# Laser_Shield_Eth.net
KiCad netlist of a schematic drawn in EAGLE
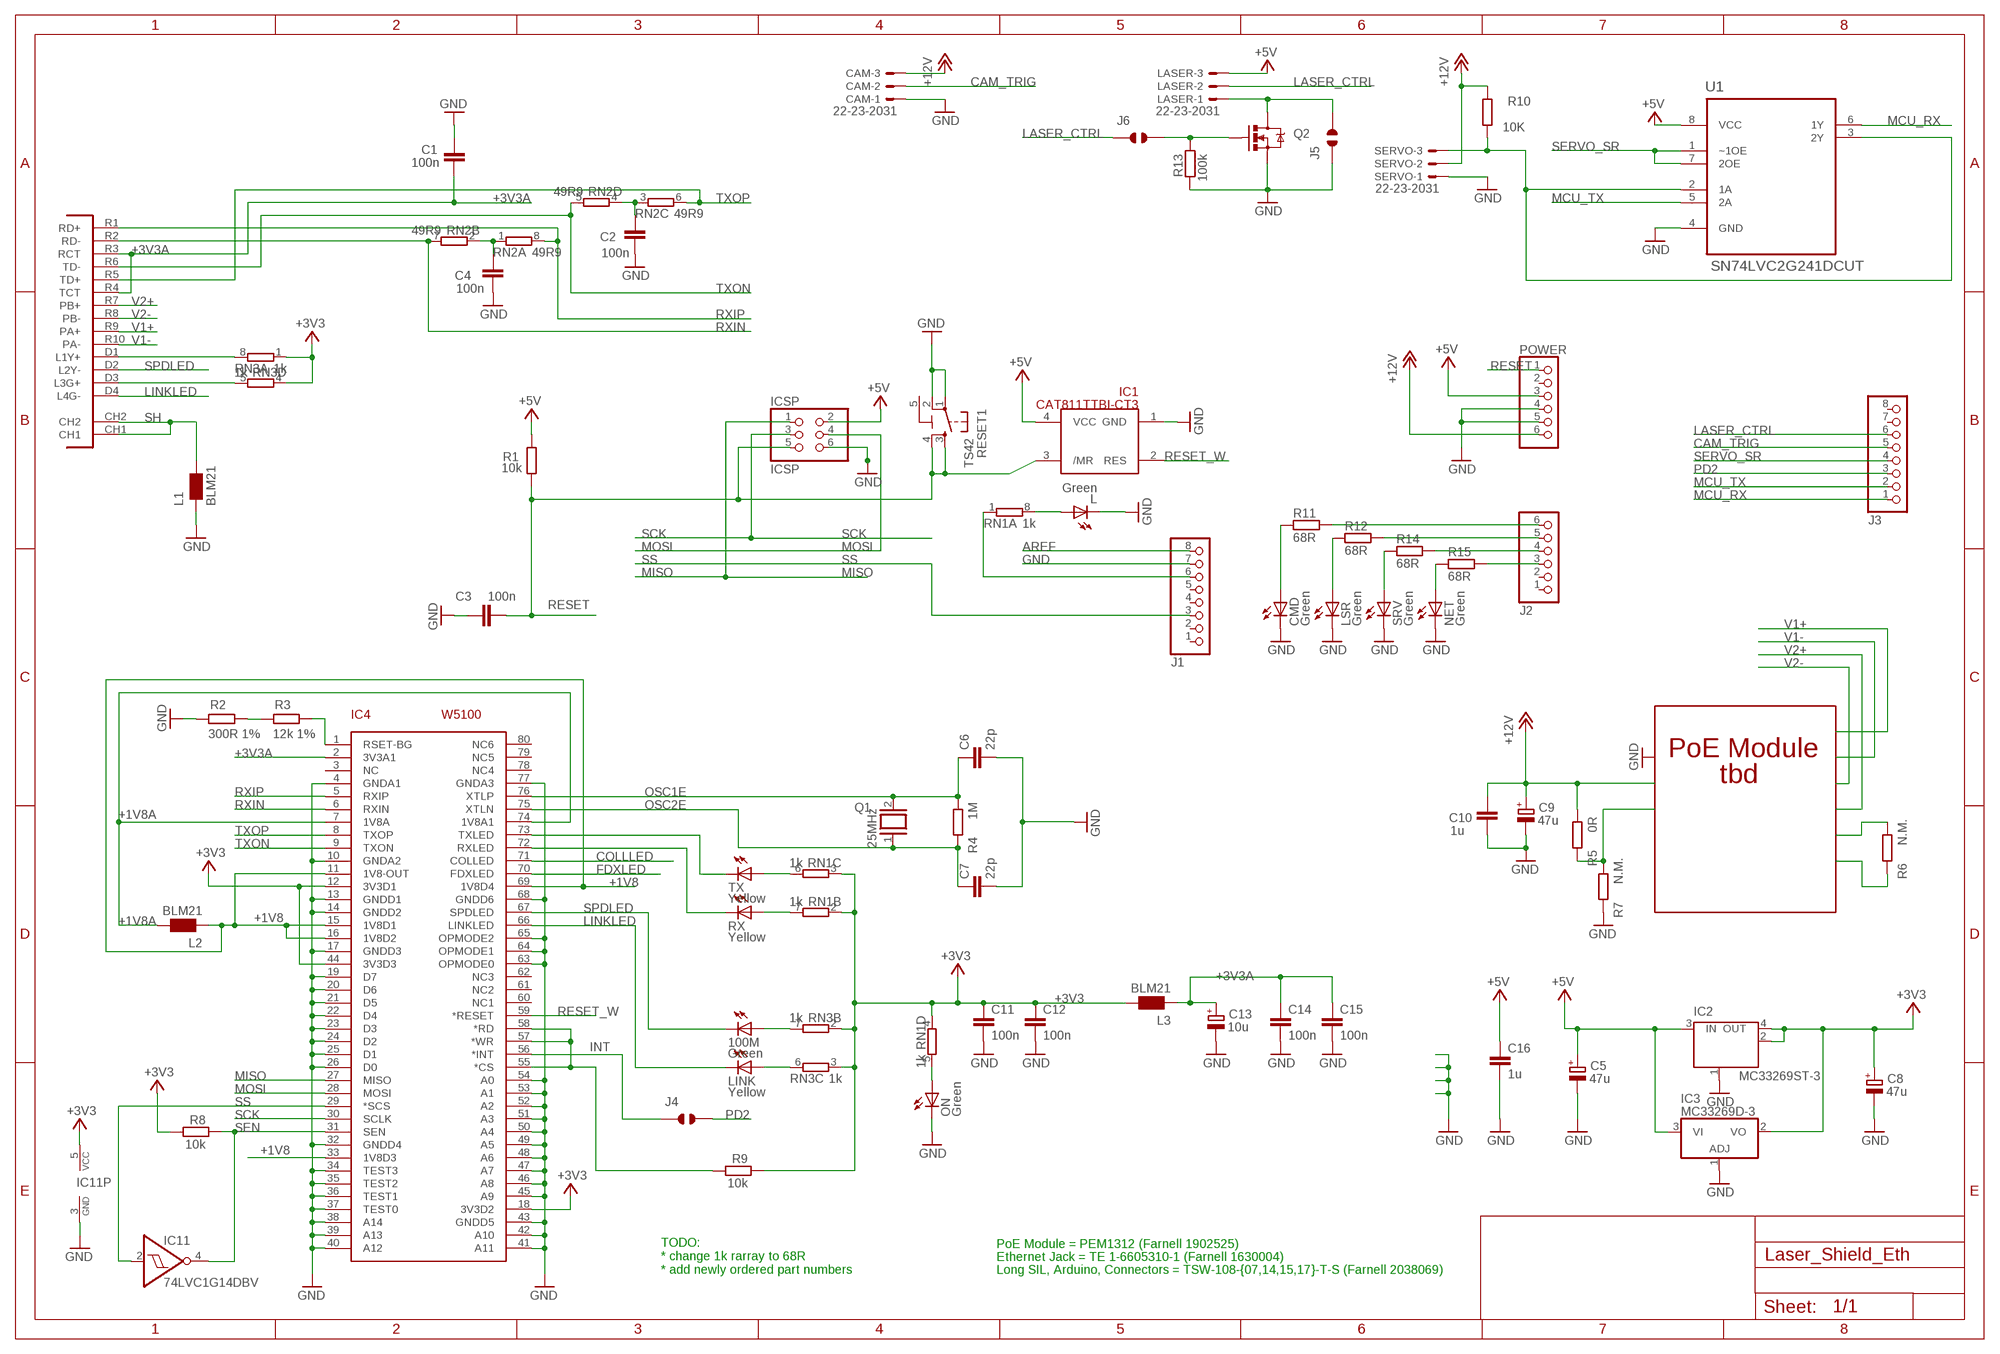
[diagram p0: schematic, sheet 1]

(export (version "E")
  (design (tool "Eeschema 10.0.6"))
  (components
    (comp (ref "100M")
      (value "Green")
      (footprint "eagle-import:CHIPLED_0805")
      (libsource (lib "eagle-import") (part "LEDCHIPLED_0805"))
    )
    (comp (ref "C1")
      (value "100n")
      (footprint "eagle-import:C0603-ROUND")
      (libsource (lib "eagle-import") (part "C-EUC0603"))
    )
    (comp (ref "C2")
      (value "100n")
      (footprint "eagle-import:C0603-ROUND")
      (libsource (lib "eagle-import") (part "C-EUC0603"))
    )
    (comp (ref "C3")
      (value "100n")
      (footprint "eagle-import:C0603-ROUND")
      (libsource (lib "eagle-import") (part "C-EUC0603"))
    )
    (comp (ref "C4")
      (value "100n")
      (footprint "eagle-import:C0603-ROUND")
      (libsource (lib "eagle-import") (part "C-EUC0603"))
    )
    (comp (ref "C5")
      (value "47u")
      (footprint "eagle-import:PANASONIC_D")
      (libsource (lib "eagle-import") (part "CPOL-EUD"))
    )
    (comp (ref "C6")
      (value "22p")
      (footprint "eagle-import:C0603-ROUND")
      (libsource (lib "eagle-import") (part "C-EUC0603"))
    )
    (comp (ref "C7")
      (value "22p")
      (footprint "eagle-import:C0603-ROUND")
      (libsource (lib "eagle-import") (part "C-EUC0603"))
    )
    (comp (ref "C8")
      (value "47u")
      (footprint "eagle-import:PANASONIC_D")
      (libsource (lib "eagle-import") (part "CPOL-EUD"))
    )
    (comp (ref "C9")
      (value "47u")
      (footprint "eagle-import:PANASONIC_D")
      (libsource (lib "eagle-import") (part "CPOL-EUD"))
    )
    (comp (ref "C10")
      (value "1u")
      (footprint "eagle-import:C0603-ROUND")
      (libsource (lib "eagle-import") (part "C-EUC0603"))
    )
    (comp (ref "C11")
      (value "100n")
      (footprint "eagle-import:C0603-ROUND")
      (libsource (lib "eagle-import") (part "C-EUC0603"))
    )
    (comp (ref "C12")
      (value "100n")
      (footprint "eagle-import:C0603-ROUND")
      (libsource (lib "eagle-import") (part "C-EUC0603"))
    )
    (comp (ref "C13")
      (value "10u")
      (footprint "eagle-import:SMC_B")
      (libsource (lib "eagle-import") (part "CPOL-EUSMCB"))
    )
    (comp (ref "C14")
      (value "100n")
      (footprint "eagle-import:C0603-ROUND")
      (libsource (lib "eagle-import") (part "C-EUC0603"))
    )
    (comp (ref "C15")
      (value "100n")
      (footprint "eagle-import:C0603-ROUND")
      (libsource (lib "eagle-import") (part "C-EUC0603"))
    )
    (comp (ref "C16")
      (value "1u")
      (footprint "eagle-import:C0603-ROUND")
      (libsource (lib "eagle-import") (part "C-EUC0603"))
    )
    (comp (ref "CAM")
      (value "22-23-2031")
      (footprint "eagle-import:22-23-2031")
      (fields (field (name "MF") "MOLEX"))
      (libsource (lib "eagle-import") (part "22-23-2031"))
    )
    (comp (ref "CMD")
      (value "Green")
      (footprint "eagle-import:CHIPLED_0805")
      (libsource (lib "eagle-import") (part "LEDCHIPLED_0805"))
    )
    (comp (ref "IC1")
      (value "CAT811TTBI-CT3")
      (footprint "eagle-import:SOT143")
      (fields (field (name "MPN") "STM812LW16F"))
      (libsource (lib "eagle-import") (part "STM812"))
    )
    (comp (ref "IC2")
      (value "MC33269ST-3")
      (footprint "eagle-import:SOT223")
      (libsource (lib "eagle-import") (part "MC33269ST-3.3T3"))
    )
    (comp (ref "IC3")
      (value "MC33269D-3")
      (footprint "eagle-import:DPACK")
      (libsource (lib "eagle-import") (part "MC33269?D-3.3"))
    )
    (comp (ref "IC4")
      (value "W5100")
      (footprint "eagle-import:SQFP-S-10X10-80")
      (libsource (lib "eagle-import") (part "W5100"))
    )
    (comp (ref "IC11")
      (value "74LVC1G14DBV")
      (footprint "eagle-import:SOT23-5")
      (fields (field (name "MPN") "SN74LVC1G14DBVT") (field (name "OC_FARNELL") "1236328"))
      (libsource (lib "eagle-import") (part "741G14DBVLVC"))
    )
    (comp (ref "ICSP")
      (value "ICSP")
      (footprint "eagle-import:2X03")
      (libsource (lib "eagle-import") (part "PINHD-2X3"))
    )
    (comp (ref "J1")
      (value "PINHD-1X8")
      (footprint "eagle-import:1X08")
      (libsource (lib "eagle-import") (part "PINHD-1X8"))
    )
    (comp (ref "J2")
      (value "PINHD-1X6")
      (footprint "eagle-import:1X06")
      (libsource (lib "eagle-import") (part "PINHD-1X6"))
    )
    (comp (ref "J3")
      (value "PINHD-1X8")
      (footprint "eagle-import:1X08")
      (libsource (lib "eagle-import") (part "PINHD-1X8"))
    )
    (comp (ref "J4")
      (value "JUMPER_SOLDER_1X2")
      (footprint "eagle-import:JUMPER_SOLDER_1X2")
      (libsource (lib "eagle-import") (part "JUMPER_SOLDER_1X2"))
    )
    (comp (ref "J5")
      (value "JUMPER_SOLDER_1X2")
      (footprint "eagle-import:JUMPER_SOLDER_1X2")
      (libsource (lib "eagle-import") (part "JUMPER_SOLDER_1X2"))
    )
    (comp (ref "J6")
      (value "JUMPER_SOLDER_1X2")
      (footprint "eagle-import:JUMPER_SOLDER_1X2")
      (libsource (lib "eagle-import") (part "JUMPER_SOLDER_1X2"))
    )
    (comp (ref "L")
      (value "Green")
      (footprint "eagle-import:CHIPLED_0805")
      (libsource (lib "eagle-import") (part "LEDCHIPLED_0805"))
    )
    (comp (ref "L1")
      (value "BLM21")
      (footprint "eagle-import:0805")
      (libsource (lib "eagle-import") (part "WE-CBF_0805"))
    )
    (comp (ref "L2")
      (value "BLM21")
      (footprint "eagle-import:0805")
      (libsource (lib "eagle-import") (part "WE-CBF_0805"))
    )
    (comp (ref "L3")
      (value "BLM21")
      (footprint "eagle-import:0805")
      (libsource (lib "eagle-import") (part "WE-CBF_0805"))
    )
    (comp (ref "LASER")
      (value "22-23-2031")
      (footprint "eagle-import:22-23-2031")
      (fields (field (name "MF") "MOLEX"))
      (libsource (lib "eagle-import") (part "22-23-2031"))
    )
    (comp (ref "LINK")
      (value "Yellow")
      (footprint "eagle-import:CHIPLED_0805")
      (libsource (lib "eagle-import") (part "LEDCHIPLED_0805"))
    )
    (comp (ref "LSR")
      (value "Green")
      (footprint "eagle-import:CHIPLED_0805")
      (libsource (lib "eagle-import") (part "LEDCHIPLED_0805"))
    )
    (comp (ref "NET")
      (value "Green")
      (footprint "eagle-import:CHIPLED_0805")
      (libsource (lib "eagle-import") (part "LEDCHIPLED_0805"))
    )
    (comp (ref "ON")
      (value "Green")
      (footprint "eagle-import:CHIPLED_0805")
      (libsource (lib "eagle-import") (part "LEDCHIPLED_0805"))
    )
    (comp (ref "POWER")
      (value "PINHD-1X6")
      (footprint "eagle-import:1X06")
      (libsource (lib "eagle-import") (part "PINHD-1X6"))
    )
    (comp (ref "Q1")
      (value "25MHz")
      (footprint "eagle-import:QS")
      (libsource (lib "eagle-import") (part "XTAL/S"))
    )
    (comp (ref "Q2")
      (value "MOSFET-NCHANNELSMD")
      (footprint "eagle-import:SOT23-3")
      (libsource (lib "eagle-import") (part "MOSFET-NCHANNELSMD"))
    )
    (comp (ref "R1")
      (value "10k")
      (footprint "eagle-import:R0603-ROUND")
      (libsource (lib "eagle-import") (part "R-EU_0603-RND"))
    )
    (comp (ref "R2")
      (value "300R 1%")
      (footprint "eagle-import:R0603-ROUND")
      (libsource (lib "eagle-import") (part "R-EU_0603-RND"))
    )
    (comp (ref "R3")
      (value "12k 1%")
      (footprint "eagle-import:R0603-ROUND")
      (libsource (lib "eagle-import") (part "R-EU_0603-RND"))
    )
    (comp (ref "R4")
      (value "1M")
      (footprint "eagle-import:R0603-ROUND")
      (libsource (lib "eagle-import") (part "R-EU_0603-RND"))
    )
    (comp (ref "R5")
      (value "0R")
      (footprint "eagle-import:R0603-ROUND")
      (libsource (lib "eagle-import") (part "R-EU_0603-RND"))
    )
    (comp (ref "R6")
      (value "N.M.")
      (footprint "eagle-import:R0603-ROUND")
      (libsource (lib "eagle-import") (part "R-EU_0603-RND"))
    )
    (comp (ref "R7")
      (value "N.M.")
      (footprint "eagle-import:R0603-ROUND")
      (libsource (lib "eagle-import") (part "R-EU_0603-RND"))
    )
    (comp (ref "R8")
      (value "10k")
      (footprint "eagle-import:R0603-ROUND")
      (libsource (lib "eagle-import") (part "R-EU_0603-RND"))
    )
    (comp (ref "R9")
      (value "10k")
      (footprint "eagle-import:R0603-ROUND")
      (libsource (lib "eagle-import") (part "R-EU_R0603"))
    )
    (comp (ref "R10")
      (value "10K")
      (footprint "eagle-import:R0603-ROUND")
      (libsource (lib "eagle-import") (part "R-EU_0603-RND"))
    )
    (comp (ref "R11")
      (value "68R")
      (footprint "eagle-import:R0603-ROUND")
      (libsource (lib "eagle-import") (part "R-EU_R0603"))
    )
    (comp (ref "R12")
      (value "68R")
      (footprint "eagle-import:R0603-ROUND")
      (libsource (lib "eagle-import") (part "R-EU_R0603"))
    )
    (comp (ref "R13")
      (value "100k")
      (footprint "eagle-import:R0603-ROUND")
      (libsource (lib "eagle-import") (part "R-EU_R0603"))
    )
    (comp (ref "R14")
      (value "68R")
      (footprint "eagle-import:R0603-ROUND")
      (libsource (lib "eagle-import") (part "R-EU_R0603"))
    )
    (comp (ref "R15")
      (value "68R")
      (footprint "eagle-import:R0603-ROUND")
      (libsource (lib "eagle-import") (part "R-EU_R0603"))
    )
    (comp (ref "RESET1")
      (value "TS42")
      (footprint "eagle-import:TS42")
      (libsource (lib "eagle-import") (part "TS42"))
    )
    (comp (ref "RN1")
      (value "1k")
      (footprint "eagle-import:CAY16")
      (fields (field (name "MPN") "CAY16-102J4LF") (field (name "OC_FARNELL") "1770133"))
      (libsource (lib "eagle-import") (part "4R-NCAY16"))
    )
    (comp (ref "RN2")
      (value "49R9")
      (footprint "eagle-import:CAY16")
      (fields (field (name "MPN") "CAY16-49R9F4LF") (field (name "OC_FARNELL") "2113092"))
      (libsource (lib "eagle-import") (part "4R-NCAY16"))
    )
    (comp (ref "RN3")
      (value "1k")
      (footprint "eagle-import:CAY16")
      (fields (field (name "MPN") "CAY16-102J4LF") (field (name "OC_FARNELL") "1770133"))
      (libsource (lib "eagle-import") (part "4R-NCAY16"))
    )
    (comp (ref "RX")
      (value "Yellow")
      (footprint "eagle-import:CHIPLED_0805")
      (libsource (lib "eagle-import") (part "LEDCHIPLED_0805"))
    )
    (comp (ref "SERVO")
      (value "22-23-2031")
      (footprint "eagle-import:22-23-2031")
      (fields
        (field (name "MF") "MOLEX")
        (field (name "MPN") "22-03-5035")
        (field (name "OC_FARNELL") "9979620")
      )
      (libsource (lib "eagle-import") (part "22-23-2031"))
    )
    (comp (ref "SRV")
      (value "Green")
      (footprint "eagle-import:CHIPLED_0805")
      (libsource (lib "eagle-import") (part "LEDCHIPLED_0805"))
    )
    (comp (ref "TX")
      (value "Yellow")
      (footprint "eagle-import:CHIPLED_0805")
      (libsource (lib "eagle-import") (part "LEDCHIPLED_0805"))
    )
    (comp (ref "U$1")
      (value "POE-RJ45")
      (footprint "eagle-import:POE-RJ45")
      (libsource (lib "eagle-import") (part "POE-RJ45"))
    )
    (comp (ref "U1")
      (value "SN74LVC2G241DCUT")
      (footprint "eagle-import:SOP50P310X90-8N")
      (libsource (lib "eagle-import") (part "SN74LVC2G241DCUT"))
    )
  )
  (nets
    (net (code "1") (name "+3V3") (class "Default")
      (node (ref "C11") (pin "1") (pinfunction "1_1") (pintype "passive"))
      (node (ref "C12") (pin "1") (pinfunction "1_1") (pintype "passive"))
      (node (ref "C8") (pin "+") (pinfunction "+_+") (pintype "passive"))
      (node (ref "IC11") (pin "5") (pinfunction "VCC_5") (pintype "power_in"))
      (node (ref "IC2") (pin "2") (pinfunction "OUT_2") (pintype "passive"))
      (node (ref "IC2") (pin "4") (pinfunction "OUT_4") (pintype "passive"))
      (node (ref "IC3") (pin "2") (pinfunction "VO_2") (pintype "passive"))
      (node (ref "IC4") (pin "12") (pinfunction "3V3D1_12") (pintype "power_in"))
      (node (ref "IC4") (pin "18") (pinfunction "3V3D2_18") (pintype "power_in"))
      (node (ref "IC4") (pin "44") (pinfunction "3V3D3_44") (pintype "power_in"))
      (node (ref "L3") (pin "2") (pinfunction "2_2") (pintype "passive"))
      (node (ref "R8") (pin "1") (pinfunction "1_1") (pintype "passive"))
      (node (ref "R9") (pin "2") (pinfunction "2_2") (pintype "passive"))
      (node (ref "RN1") (pin "2") (pinfunction "1_2") (pintype "passive"))
      (node (ref "RN1") (pin "3") (pinfunction "1_3") (pintype "passive"))
      (node (ref "RN1") (pin "4") (pinfunction "1_4") (pintype "passive"))
      (node (ref "RN3") (pin "1") (pinfunction "1_1") (pintype "passive"))
      (node (ref "RN3") (pin "2") (pinfunction "1_2") (pintype "passive"))
      (node (ref "RN3") (pin "3") (pinfunction "1_3") (pintype "passive"))
      (node (ref "RN3") (pin "4") (pinfunction "1_4") (pintype "passive"))
    )
    (net (code "2") (name "+5V") (class "Default")
      (node (ref "C16") (pin "1") (pinfunction "1_1") (pintype "passive"))
      (node (ref "C5") (pin "+") (pinfunction "+_+") (pintype "passive"))
      (node (ref "IC1") (pin "4") (pinfunction "VCC_4") (pintype "power_in"))
      (node (ref "IC2") (pin "3") (pinfunction "IN_3") (pintype "input"))
      (node (ref "IC3") (pin "3") (pinfunction "VI_3") (pintype "input"))
      (node (ref "ICSP") (pin "2") (pinfunction "2_2") (pintype "passive"))
      (node (ref "LASER") (pin "3") (pinfunction "S_3") (pintype "passive"))
      (node (ref "POWER") (pin "3") (pinfunction "3_3") (pintype "passive"))
      (node (ref "R1") (pin "2") (pinfunction "2_2") (pintype "passive"))
      (node (ref "U1") (pin "8") (pinfunction "VCC_8") (pintype "power_in"))
    )
    (net (code "3") (name "+12V") (class "Default")
      (node (ref "C10") (pin "2") (pinfunction "2_2") (pintype "passive"))
      (node (ref "C9") (pin "+") (pinfunction "+_+") (pintype "passive"))
      (node (ref "CAM") (pin "3") (pinfunction "S_3") (pintype "passive"))
      (node (ref "POWER") (pin "6") (pinfunction "6_6") (pintype "passive"))
      (node (ref "R10") (pin "1") (pinfunction "1_1") (pintype "passive"))
      (node (ref "R5") (pin "1") (pinfunction "1_1") (pintype "passive"))
      (node (ref "SERVO") (pin "2") (pinfunction "S_2") (pintype "passive"))
    )
    (net (code "4") (name "/+1V8") (class "Default")
      (node (ref "IC4") (pin "11") (pinfunction "1V8-OUT_11") (pintype "power_in"))
      (node (ref "IC4") (pin "15") (pinfunction "1V8D1_15") (pintype "power_in"))
      (node (ref "IC4") (pin "16") (pinfunction "1V8D2_16") (pintype "power_in"))
      (node (ref "IC4") (pin "33") (pinfunction "1V8D3_33") (pintype "power_in"))
      (node (ref "IC4") (pin "69") (pinfunction "1V8D4_69") (pintype "power_in"))
      (node (ref "L2") (pin "1") (pinfunction "1_1") (pintype "passive"))
    )
    (net (code "5") (name "/+1V8A") (class "Default")
      (node (ref "IC4") (pin "7") (pinfunction "1V8A_7") (pintype "power_in"))
      (node (ref "IC4") (pin "74") (pinfunction "1V8A1_74") (pintype "power_in"))
      (node (ref "L2") (pin "2") (pinfunction "2_2") (pintype "passive"))
    )
    (net (code "6") (name "/+3V3A") (class "Default")
      (node (ref "C1") (pin "1") (pinfunction "1_1") (pintype "passive"))
      (node (ref "C13") (pin "+") (pinfunction "+_+") (pintype "passive"))
      (node (ref "C14") (pin "1") (pinfunction "1_1") (pintype "passive"))
      (node (ref "C15") (pin "1") (pinfunction "1_1") (pintype "passive"))
      (node (ref "IC4") (pin "2") (pinfunction "3V3A1_2") (pintype "power_in"))
      (node (ref "L3") (pin "1") (pinfunction "1_1") (pintype "passive"))
      (node (ref "U$1") (pin "R3") (pinfunction "RCT_R3") (pintype "bidirectional"))
      (node (ref "U$1") (pin "R4") (pinfunction "TCT_R4") (pintype "bidirectional"))
    )
    (net (code "7") (name "/5-GND") (class "Default")
      (node (ref "RESET1") (pin "5") (pinfunction "5-GND_5") (pintype "power_in"))
    )
    (net (code "8") (name "/AREF") (class "Default")
      (node (ref "J1") (pin "8") (pinfunction "8_8") (pintype "passive"))
    )
    (net (code "9") (name "/CAM_TRIG") (class "Default")
      (node (ref "CAM") (pin "2") (pinfunction "S_2") (pintype "passive"))
      (node (ref "J3") (pin "5") (pinfunction "5_5") (pintype "passive"))
    )
    (net (code "10") (name "/COLLLED") (class "Default")
      (node (ref "IC4") (pin "71") (pinfunction "COLLED_71") (pintype "output"))
    )
    (net (code "11") (name "/FDXLED") (class "Default")
      (node (ref "IC4") (pin "70") (pinfunction "FDXLED_70") (pintype "output"))
    )
    (net (code "12") (name "/INT") (class "Default")
      (node (ref "IC4") (pin "56") (pinfunction "*INT_56") (pintype "input"))
      (node (ref "J4") (pin "1") (pinfunction "1_1") (pintype "passive"))
    )
    (net (code "13") (name "/LASER_CTRL") (class "Default")
      (node (ref "J3") (pin "6") (pinfunction "6_6") (pintype "passive"))
      (node (ref "J6") (pin "1") (pinfunction "1_1") (pintype "passive"))
      (node (ref "LASER") (pin "2") (pinfunction "S_2") (pintype "passive"))
    )
    (net (code "14") (name "/LINKLED") (class "Default")
      (node (ref "IC4") (pin "66") (pinfunction "LINKLED_66") (pintype "output"))
      (node (ref "LINK") (pin "C") (pinfunction "C_C") (pintype "passive"))
      (node (ref "U$1") (pin "D4") (pinfunction "L4G-_D4") (pintype "bidirectional"))
    )
    (net (code "15") (name "/MCU_RX") (class "Default")
      (node (ref "J3") (pin "1") (pinfunction "1_1") (pintype "passive"))
      (node (ref "U1") (pin "6") (pinfunction "1Y_6") (pintype "output"))
    )
    (net (code "16") (name "/MCU_TX") (class "Default")
      (node (ref "J3") (pin "2") (pinfunction "2_2") (pintype "passive"))
      (node (ref "U1") (pin "5") (pinfunction "2A_5") (pintype "input"))
    )
    (net (code "17") (name "/MISO") (class "Default")
      (node (ref "IC4") (pin "27") (pinfunction "MISO_27") (pintype "input"))
      (node (ref "ICSP") (pin "1") (pinfunction "1_1") (pintype "passive"))
    )
    (net (code "18") (name "/MOSI") (class "Default")
      (node (ref "IC4") (pin "28") (pinfunction "MOSI_28") (pintype "output"))
      (node (ref "ICSP") (pin "4") (pinfunction "4_4") (pintype "passive"))
    )
    (net (code "19") (name "/OSC1E") (class "Default")
      (node (ref "C6") (pin "1") (pinfunction "1_1") (pintype "passive"))
      (node (ref "IC4") (pin "76") (pinfunction "XTLP_76") (pintype "output"))
      (node (ref "Q1") (pin "2") (pinfunction "2_2") (pintype "passive"))
      (node (ref "R4") (pin "1") (pinfunction "1_1") (pintype "passive"))
    )
    (net (code "20") (name "/OSC2E") (class "Default")
      (node (ref "C7") (pin "1") (pinfunction "1_1") (pintype "passive"))
      (node (ref "IC4") (pin "75") (pinfunction "XTLN_75") (pintype "output"))
      (node (ref "Q1") (pin "1") (pinfunction "1_1") (pintype "passive"))
      (node (ref "R4") (pin "2") (pinfunction "2_2") (pintype "passive"))
    )
    (net (code "21") (name "/PD2") (class "Default")
      (node (ref "J3") (pin "3") (pinfunction "3_3") (pintype "passive"))
      (node (ref "J4") (pin "2") (pinfunction "2_2") (pintype "passive"))
    )
    (net (code "22") (name "/RESET") (class "Default")
      (node (ref "C3") (pin "1") (pinfunction "1_1") (pintype "passive"))
      (node (ref "IC1") (pin "3") (pinfunction "/MR_3") (pintype "input"))
      (node (ref "ICSP") (pin "5") (pinfunction "5_5") (pintype "passive"))
      (node (ref "POWER") (pin "1") (pinfunction "1_1") (pintype "passive"))
      (node (ref "R1") (pin "1") (pinfunction "1_1") (pintype "passive"))
      (node (ref "RESET1") (pin "3") (pinfunction "3_3") (pintype "passive"))
      (node (ref "RESET1") (pin "4") (pinfunction "4_4") (pintype "passive"))
    )
    (net (code "23") (name "/RESET_W") (class "Default")
      (node (ref "IC1") (pin "2") (pinfunction "RES_2") (pintype "output"))
      (node (ref "IC4") (pin "59") (pinfunction "*RESET_59") (pintype "input"))
    )
    (net (code "24") (name "/RXIN") (class "Default")
      (node (ref "IC4") (pin "6") (pinfunction "RXIN_6") (pintype "input"))
      (node (ref "RN2") (pin "7") (pinfunction "2_7") (pintype "passive"))
      (node (ref "U$1") (pin "R2") (pinfunction "RD-_R2") (pintype "bidirectional"))
    )
    (net (code "25") (name "/RXIP") (class "Default")
      (node (ref "IC4") (pin "5") (pinfunction "RXIP_5") (pintype "input"))
      (node (ref "RN2") (pin "8") (pinfunction "2_8") (pintype "passive"))
      (node (ref "U$1") (pin "R1") (pinfunction "RD+_R1") (pintype "bidirectional"))
    )
    (net (code "26") (name "/SCK") (class "Default")
      (node (ref "IC4") (pin "30") (pinfunction "SCLK_30") (pintype "input"))
      (node (ref "ICSP") (pin "3") (pinfunction "3_3") (pintype "passive"))
    )
    (net (code "27") (name "/SEN") (class "Default")
      (node (ref "IC11") (pin "4") (pinfunction "O_4") (pintype "output"))
      (node (ref "IC4") (pin "31") (pinfunction "SEN_31") (pintype "input"))
      (node (ref "R8") (pin "2") (pinfunction "2_2") (pintype "passive"))
    )
    (net (code "28") (name "/SERVO_SR") (class "Default")
      (node (ref "J3") (pin "4") (pinfunction "4_4") (pintype "passive"))
      (node (ref "U1") (pin "1") (pinfunction "~{1OE}_1") (pintype "input"))
      (node (ref "U1") (pin "7") (pinfunction "2OE_7") (pintype "input"))
    )
    (net (code "29") (name "/SH") (class "Default")
      (node (ref "L1") (pin "2") (pinfunction "2_2") (pintype "passive"))
      (node (ref "U$1") (pin "CH1") (pinfunction "CH1_CH1") (pintype "bidirectional"))
      (node (ref "U$1") (pin "CH2") (pinfunction "CH2_CH2") (pintype "bidirectional"))
    )
    (net (code "30") (name "/SPDLED") (class "Default")
      (node (ref "100M") (pin "C") (pinfunction "C_C") (pintype "passive"))
      (node (ref "IC4") (pin "67") (pinfunction "SPDLED_67") (pintype "output"))
      (node (ref "U$1") (pin "D2") (pinfunction "L2Y-_D2") (pintype "bidirectional"))
    )
    (net (code "31") (name "/SS") (class "Default")
      (node (ref "IC11") (pin "2") (pinfunction "I_2") (pintype "input"))
      (node (ref "IC4") (pin "29") (pinfunction "*SCS_29") (pintype "input"))
      (node (ref "J1") (pin "3") (pinfunction "3_3") (pintype "passive"))
    )
    (net (code "32") (name "/TXON") (class "Default")
      (node (ref "IC4") (pin "9") (pinfunction "TXON_9") (pintype "output"))
      (node (ref "RN2") (pin "5") (pinfunction "2_5") (pintype "passive"))
      (node (ref "U$1") (pin "R6") (pinfunction "TD-_R6") (pintype "bidirectional"))
    )
    (net (code "33") (name "/TXOP") (class "Default")
      (node (ref "IC4") (pin "8") (pinfunction "TXOP_8") (pintype "output"))
      (node (ref "RN2") (pin "6") (pinfunction "2_6") (pintype "passive"))
      (node (ref "U$1") (pin "R5") (pinfunction "TD+_R5") (pintype "bidirectional"))
    )
    (net (code "34") (name "/V1+") (class "Default")
      (node (ref "U$1") (pin "R9") (pinfunction "PA+_R9") (pintype "bidirectional"))
    )
    (net (code "35") (name "/V1-") (class "Default")
      (node (ref "U$1") (pin "R10") (pinfunction "PA-_R10") (pintype "bidirectional"))
    )
    (net (code "36") (name "/V2+") (class "Default")
      (node (ref "U$1") (pin "R7") (pinfunction "PB+_R7") (pintype "bidirectional"))
    )
    (net (code "37") (name "/V2-") (class "Default")
      (node (ref "U$1") (pin "R8") (pinfunction "PB-_R8") (pintype "bidirectional"))
    )
    (net (code "38") (name "GND") (class "Default")
      (node (ref "C1") (pin "2") (pinfunction "2_2") (pintype "passive"))
      (node (ref "C10") (pin "1") (pinfunction "1_1") (pintype "passive"))
      (node (ref "C11") (pin "2") (pinfunction "2_2") (pintype "passive"))
      (node (ref "C12") (pin "2") (pinfunction "2_2") (pintype "passive"))
      (node (ref "C13") (pin "-") (pinfunction "-_-") (pintype "passive"))
      (node (ref "C14") (pin "2") (pinfunction "2_2") (pintype "passive"))
      (node (ref "C15") (pin "2") (pinfunction "2_2") (pintype "passive"))
      (node (ref "C16") (pin "2") (pinfunction "2_2") (pintype "passive"))
      (node (ref "C2") (pin "1") (pinfunction "1_1") (pintype "passive"))
      (node (ref "C3") (pin "2") (pinfunction "2_2") (pintype "passive"))
      (node (ref "C4") (pin "1") (pinfunction "1_1") (pintype "passive"))
      (node (ref "C5") (pin "-") (pinfunction "-_-") (pintype "passive"))
      (node (ref "C6") (pin "2") (pinfunction "2_2") (pintype "passive"))
      (node (ref "C7") (pin "2") (pinfunction "2_2") (pintype "passive"))
      (node (ref "C8") (pin "-") (pinfunction "-_-") (pintype "passive"))
      (node (ref "C9") (pin "-") (pinfunction "-_-") (pintype "passive"))
      (node (ref "CAM") (pin "1") (pinfunction "S_1") (pintype "passive"))
      (node (ref "CMD") (pin "C") (pinfunction "C_C") (pintype "passive"))
      (node (ref "IC1") (pin "1") (pinfunction "GND_1") (pintype "power_in"))
      (node (ref "IC11") (pin "3") (pinfunction "GND_3") (pintype "power_in"))
      (node (ref "IC2") (pin "1") (pinfunction "GND/ADJ_1") (pintype "input"))
      (node (ref "IC3") (pin "1") (pinfunction "ADJ_1") (pintype "input"))
      (node (ref "IC4") (pin "10") (pinfunction "GNDA2_10") (pintype "power_in"))
      (node (ref "IC4") (pin "13") (pinfunction "GNDD1_13") (pintype "power_in"))
      (node (ref "IC4") (pin "14") (pinfunction "GNDD2_14") (pintype "power_in"))
      (node (ref "IC4") (pin "17") (pinfunction "GNDD3_17") (pintype "power_in"))
      (node (ref "IC4") (pin "19") (pinfunction "D7_19") (pintype "input"))
      (node (ref "IC4") (pin "20") (pinfunction "D6_20") (pintype "input"))
      (node (ref "IC4") (pin "21") (pinfunction "D5_21") (pintype "input"))
      (node (ref "IC4") (pin "22") (pinfunction "D4_22") (pintype "input"))
      (node (ref "IC4") (pin "23") (pinfunction "D3_23") (pintype "input"))
      (node (ref "IC4") (pin "24") (pinfunction "D2_24") (pintype "input"))
      (node (ref "IC4") (pin "25") (pinfunction "D1_25") (pintype "input"))
      (node (ref "IC4") (pin "26") (pinfunction "D0_26") (pintype "input"))
      (node (ref "IC4") (pin "32") (pinfunction "GNDD4_32") (pintype "power_in"))
      (node (ref "IC4") (pin "34") (pinfunction "TEST3_34") (pintype "input"))
      (node (ref "IC4") (pin "35") (pinfunction "TEST2_35") (pintype "input"))
      (node (ref "IC4") (pin "36") (pinfunction "TEST1_36") (pintype "input"))
      (node (ref "IC4") (pin "37") (pinfunction "TEST0_37") (pintype "input"))
      (node (ref "IC4") (pin "38") (pinfunction "A14_38") (pintype "input"))
      (node (ref "IC4") (pin "39") (pinfunction "A13_39") (pintype "input"))
      (node (ref "IC4") (pin "4") (pinfunction "GNDA1_4") (pintype "power_in"))
      (node (ref "IC4") (pin "40") (pinfunction "A12_40") (pintype "input"))
      (node (ref "IC4") (pin "41") (pinfunction "A11_41") (pintype "input"))
      (node (ref "IC4") (pin "42") (pinfunction "A10_42") (pintype "input"))
      (node (ref "IC4") (pin "43") (pinfunction "GNDD5_43") (pintype "power_in"))
      (node (ref "IC4") (pin "45") (pinfunction "A9_45") (pintype "input"))
      (node (ref "IC4") (pin "46") (pinfunction "A8_46") (pintype "input"))
      (node (ref "IC4") (pin "47") (pinfunction "A7_47") (pintype "input"))
      (node (ref "IC4") (pin "48") (pinfunction "A6_48") (pintype "input"))
      (node (ref "IC4") (pin "49") (pinfunction "A5_49") (pintype "input"))
      (node (ref "IC4") (pin "50") (pinfunction "A4_50") (pintype "input"))
      (node (ref "IC4") (pin "51") (pinfunction "A3_51") (pintype "input"))
      (node (ref "IC4") (pin "52") (pinfunction "A2_52") (pintype "input"))
      (node (ref "IC4") (pin "53") (pinfunction "A1_53") (pintype "input"))
      (node (ref "IC4") (pin "54") (pinfunction "A0_54") (pintype "input"))
      (node (ref "IC4") (pin "63") (pinfunction "OPMODE0_63") (pintype "input"))
      (node (ref "IC4") (pin "64") (pinfunction "OPMODE1_64") (pintype "input"))
      (node (ref "IC4") (pin "65") (pinfunction "OPMODE2_65") (pintype "input"))
      (node (ref "IC4") (pin "68") (pinfunction "GNDD6_68") (pintype "power_in"))
      (node (ref "IC4") (pin "77") (pinfunction "GNDA3_77") (pintype "power_in"))
      (node (ref "ICSP") (pin "6") (pinfunction "6_6") (pintype "passive"))
      (node (ref "J1") (pin "7") (pinfunction "7_7") (pintype "passive"))
      (node (ref "J5") (pin "1") (pinfunction "1_1") (pintype "passive"))
      (node (ref "L") (pin "C") (pinfunction "C_C") (pintype "passive"))
      (node (ref "L1") (pin "1") (pinfunction "1_1") (pintype "passive"))
      (node (ref "LSR") (pin "C") (pinfunction "C_C") (pintype "passive"))
      (node (ref "NET") (pin "C") (pinfunction "C_C") (pintype "passive"))
      (node (ref "ON") (pin "C") (pinfunction "C_C") (pintype "passive"))
      (node (ref "POWER") (pin "4") (pinfunction "4_4") (pintype "passive"))
      (node (ref "POWER") (pin "5") (pinfunction "5_5") (pintype "passive"))
      (node (ref "Q2") (pin "2") (pinfunction "S_2") (pintype "passive"))
      (node (ref "R13") (pin "1") (pinfunction "1_1") (pintype "passive"))
      (node (ref "R2") (pin "2") (pinfunction "2_2") (pintype "passive"))
      (node (ref "R7") (pin "2") (pinfunction "2_2") (pintype "passive"))
      (node (ref "RESET1") (pin "1") (pinfunction "1_1") (pintype "passive"))
      (node (ref "RESET1") (pin "2") (pinfunction "2_2") (pintype "passive"))
      (node (ref "SERVO") (pin "1") (pinfunction "S_1") (pintype "passive"))
      (node (ref "SRV") (pin "C") (pinfunction "C_C") (pintype "passive"))
      (node (ref "U1") (pin "4") (pinfunction "GND_4") (pintype "passive"))
    )
    (net (code "39") (name "Net-(CMD-PadA)") (class "Default")
      (node (ref "CMD") (pin "A") (pinfunction "A_A") (pintype "passive"))
      (node (ref "R11") (pin "1") (pinfunction "1_1") (pintype "passive"))
    )
    (net (code "40") (name "Net-(IC4-*CS)") (class "Default")
      (node (ref "IC4") (pin "55") (pinfunction "*CS_55") (pintype "input"))
      (node (ref "IC4") (pin "57") (pinfunction "*WR_57") (pintype "input"))
      (node (ref "IC4") (pin "58") (pinfunction "*RD_58") (pintype "input"))
      (node (ref "R9") (pin "1") (pinfunction "1_1") (pintype "passive"))
    )
    (net (code "41") (name "Net-(IC4-RSET-BG)") (class "Default")
      (node (ref "IC4") (pin "1") (pinfunction "RSET-BG_1") (pintype "input"))
      (node (ref "R3") (pin "1") (pinfunction "1_1") (pintype "passive"))
    )
    (net (code "42") (name "Net-(IC4-RXLED)") (class "Default")
      (node (ref "IC4") (pin "72") (pinfunction "RXLED_72") (pintype "output"))
      (node (ref "RX") (pin "C") (pinfunction "C_C") (pintype "passive"))
    )
    (net (code "43") (name "Net-(IC4-TXLED)") (class "Default")
      (node (ref "IC4") (pin "73") (pinfunction "TXLED_73") (pintype "output"))
      (node (ref "TX") (pin "C") (pinfunction "C_C") (pintype "passive"))
    )
    (net (code "44") (name "Net-(J1-Pad6)") (class "Default")
      (node (ref "J1") (pin "6") (pinfunction "6_6") (pintype "passive"))
      (node (ref "RN1") (pin "1") (pinfunction "1_1") (pintype "passive"))
    )
    (net (code "45") (name "Net-(J2-Pad3)") (class "Default")
      (node (ref "J2") (pin "3") (pinfunction "3_3") (pintype "passive"))
      (node (ref "R15") (pin "2") (pinfunction "2_2") (pintype "passive"))
    )
    (net (code "46") (name "Net-(J2-Pad4)") (class "Default")
      (node (ref "J2") (pin "4") (pinfunction "4_4") (pintype "passive"))
      (node (ref "R14") (pin "2") (pinfunction "2_2") (pintype "passive"))
    )
    (net (code "47") (name "Net-(J2-Pad5)") (class "Default")
      (node (ref "J2") (pin "5") (pinfunction "5_5") (pintype "passive"))
      (node (ref "R12") (pin "2") (pinfunction "2_2") (pintype "passive"))
    )
    (net (code "48") (name "Net-(J2-Pad6)") (class "Default")
      (node (ref "J2") (pin "6") (pinfunction "6_6") (pintype "passive"))
      (node (ref "R11") (pin "2") (pinfunction "2_2") (pintype "passive"))
    )
    (net (code "49") (name "Net-(LASERA-S)") (class "Default")
      (node (ref "J5") (pin "2") (pinfunction "2_2") (pintype "passive"))
      (node (ref "LASER") (pin "1") (pinfunction "S_1") (pintype "passive"))
      (node (ref "Q2") (pin "3") (pinfunction "D_3") (pintype "passive"))
    )
    (net (code "50") (name "Net-(LSR-PadA)") (class "Default")
      (node (ref "LSR") (pin "A") (pinfunction "A_A") (pintype "passive"))
      (node (ref "R12") (pin "1") (pinfunction "1_1") (pintype "passive"))
    )
    (net (code "51") (name "Net-(NET-PadA)") (class "Default")
      (node (ref "NET") (pin "A") (pinfunction "A_A") (pintype "passive"))
      (node (ref "R15") (pin "1") (pinfunction "1_1") (pintype "passive"))
    )
    (net (code "52") (name "Net-(Q2-G)") (class "Default")
      (node (ref "J6") (pin "2") (pinfunction "2_2") (pintype "passive"))
      (node (ref "Q2") (pin "1") (pinfunction "G_1") (pintype "passive"))
      (node (ref "R13") (pin "2") (pinfunction "2_2") (pintype "passive"))
    )
    (net (code "53") (name "Net-(R2-Pad1)") (class "Default")
      (node (ref "R2") (pin "1") (pinfunction "1_1") (pintype "passive"))
      (node (ref "R3") (pin "2") (pinfunction "2_2") (pintype "passive"))
    )
    (net (code "54") (name "Net-(R5-Pad2)") (class "Default")
      (node (ref "R5") (pin "2") (pinfunction "2_2") (pintype "passive"))
      (node (ref "R7") (pin "1") (pinfunction "1_1") (pintype "passive"))
    )
    (net (code "55") (name "Net-(R14-Pad1)") (class "Default")
      (node (ref "R14") (pin "1") (pinfunction "1_1") (pintype "passive"))
      (node (ref "SRV") (pin "A") (pinfunction "A_A") (pintype "passive"))
    )
    (net (code "56") (name "Net-(RN1A-2)") (class "Default")
      (node (ref "L") (pin "A") (pinfunction "A_A") (pintype "passive"))
      (node (ref "RN1") (pin "8") (pinfunction "2_8") (pintype "passive"))
    )
    (net (code "57") (name "Net-(RN1B-2)") (class "Default")
      (node (ref "RN1") (pin "7") (pinfunction "2_7") (pintype "passive"))
      (node (ref "RX") (pin "A") (pinfunction "A_A") (pintype "passive"))
    )
    (net (code "58") (name "Net-(RN1C-2)") (class "Default")
      (node (ref "RN1") (pin "6") (pinfunction "2_6") (pintype "passive"))
      (node (ref "TX") (pin "A") (pinfunction "A_A") (pintype "passive"))
    )
    (net (code "59") (name "Net-(RN1D-2)") (class "Default")
      (node (ref "ON") (pin "A") (pinfunction "A_A") (pintype "passive"))
      (node (ref "RN1") (pin "5") (pinfunction "2_5") (pintype "passive"))
    )
    (net (code "60") (name "Net-(RN2B-1)") (class "Default")
      (node (ref "C4") (pin "2") (pinfunction "2_2") (pintype "passive"))
      (node (ref "RN2") (pin "1") (pinfunction "1_1") (pintype "passive"))
      (node (ref "RN2") (pin "2") (pinfunction "1_2") (pintype "passive"))
    )
    (net (code "61") (name "Net-(RN2C-1)") (class "Default")
      (node (ref "C2") (pin "2") (pinfunction "2_2") (pintype "passive"))
      (node (ref "RN2") (pin "3") (pinfunction "1_3") (pintype "passive"))
      (node (ref "RN2") (pin "4") (pinfunction "1_4") (pintype "passive"))
    )
    (net (code "62") (name "Net-(RN3A-2)") (class "Default")
      (node (ref "RN3") (pin "8") (pinfunction "2_8") (pintype "passive"))
      (node (ref "U$1") (pin "D1") (pinfunction "L1Y+_D1") (pintype "bidirectional"))
    )
    (net (code "63") (name "Net-(RN3B-2)") (class "Default")
      (node (ref "100M") (pin "A") (pinfunction "A_A") (pintype "passive"))
      (node (ref "RN3") (pin "7") (pinfunction "2_7") (pintype "passive"))
    )
    (net (code "64") (name "Net-(RN3C-2)") (class "Default")
      (node (ref "LINK") (pin "A") (pinfunction "A_A") (pintype "passive"))
      (node (ref "RN3") (pin "6") (pinfunction "2_6") (pintype "passive"))
    )
    (net (code "65") (name "Net-(RN3D-2)") (class "Default")
      (node (ref "RN3") (pin "5") (pinfunction "2_5") (pintype "passive"))
      (node (ref "U$1") (pin "D3") (pinfunction "L3G+_D3") (pintype "bidirectional"))
    )
    (net (code "66") (name "Net-(SERVOC-S)") (class "Default")
      (node (ref "R10") (pin "2") (pinfunction "2_2") (pintype "passive"))
      (node (ref "SERVO") (pin "3") (pinfunction "S_3") (pintype "passive"))
      (node (ref "U1") (pin "2") (pinfunction "1A_2") (pintype "input"))
      (node (ref "U1") (pin "3") (pinfunction "2Y_3") (pintype "output"))
    )
    (net (code "67") (name "unconnected-(IC4-NC-Pad3)") (class "Default")
      (node (ref "IC4") (pin "3") (pinfunction "NC_3") (pintype "no_connect"))
    )
    (net (code "68") (name "unconnected-(IC4-NC1-Pad60)") (class "Default")
      (node (ref "IC4") (pin "60") (pinfunction "NC1_60") (pintype "no_connect"))
    )
    (net (code "69") (name "unconnected-(IC4-NC2-Pad61)") (class "Default")
      (node (ref "IC4") (pin "61") (pinfunction "NC2_61") (pintype "no_connect"))
    )
    (net (code "70") (name "unconnected-(IC4-NC3-Pad62)") (class "Default")
      (node (ref "IC4") (pin "62") (pinfunction "NC3_62") (pintype "no_connect"))
    )
    (net (code "71") (name "unconnected-(IC4-NC4-Pad78)") (class "Default")
      (node (ref "IC4") (pin "78") (pinfunction "NC4_78") (pintype "no_connect"))
    )
    (net (code "72") (name "unconnected-(IC4-NC5-Pad79)") (class "Default")
      (node (ref "IC4") (pin "79") (pinfunction "NC5_79") (pintype "no_connect"))
    )
    (net (code "73") (name "unconnected-(IC4-NC6-Pad80)") (class "Default")
      (node (ref "IC4") (pin "80") (pinfunction "NC6_80") (pintype "no_connect"))
    )
    (net (code "74") (name "unconnected-(J1-Pad1)") (class "Default")
      (node (ref "J1") (pin "1") (pinfunction "1_1") (pintype "passive"))
    )
    (net (code "75") (name "unconnected-(J1-Pad2)") (class "Default")
      (node (ref "J1") (pin "2") (pinfunction "2_2") (pintype "passive"))
    )
    (net (code "76") (name "unconnected-(J1-Pad4)") (class "Default")
      (node (ref "J1") (pin "4") (pinfunction "4_4") (pintype "passive"))
    )
    (net (code "77") (name "unconnected-(J1-Pad5)") (class "Default")
      (node (ref "J1") (pin "5") (pinfunction "5_5") (pintype "passive"))
    )
    (net (code "78") (name "unconnected-(J2-Pad1)") (class "Default")
      (node (ref "J2") (pin "1") (pinfunction "1_1") (pintype "passive"))
    )
    (net (code "79") (name "unconnected-(J2-Pad2)") (class "Default")
      (node (ref "J2") (pin "2") (pinfunction "2_2") (pintype "passive"))
    )
    (net (code "80") (name "unconnected-(J3-Pad7)") (class "Default")
      (node (ref "J3") (pin "7") (pinfunction "7_7") (pintype "passive"))
    )
    (net (code "81") (name "unconnected-(J3-Pad8)") (class "Default")
      (node (ref "J3") (pin "8") (pinfunction "8_8") (pintype "passive"))
    )
    (net (code "82") (name "unconnected-(POWER-Pad2)") (class "Default")
      (node (ref "POWER") (pin "2") (pinfunction "2_2") (pintype "passive"))
    )
    (net (code "83") (name "unconnected-(R6-Pad1)") (class "Default")
      (node (ref "R6") (pin "1") (pinfunction "1_1") (pintype "passive"))
    )
    (net (code "84") (name "unconnected-(R6-Pad2)") (class "Default")
      (node (ref "R6") (pin "2") (pinfunction "2_2") (pintype "passive"))
    )
  )
)
